# RcMPPT-Power_Module.net
KiCad netlist of a schematic drawn in Altium Designer
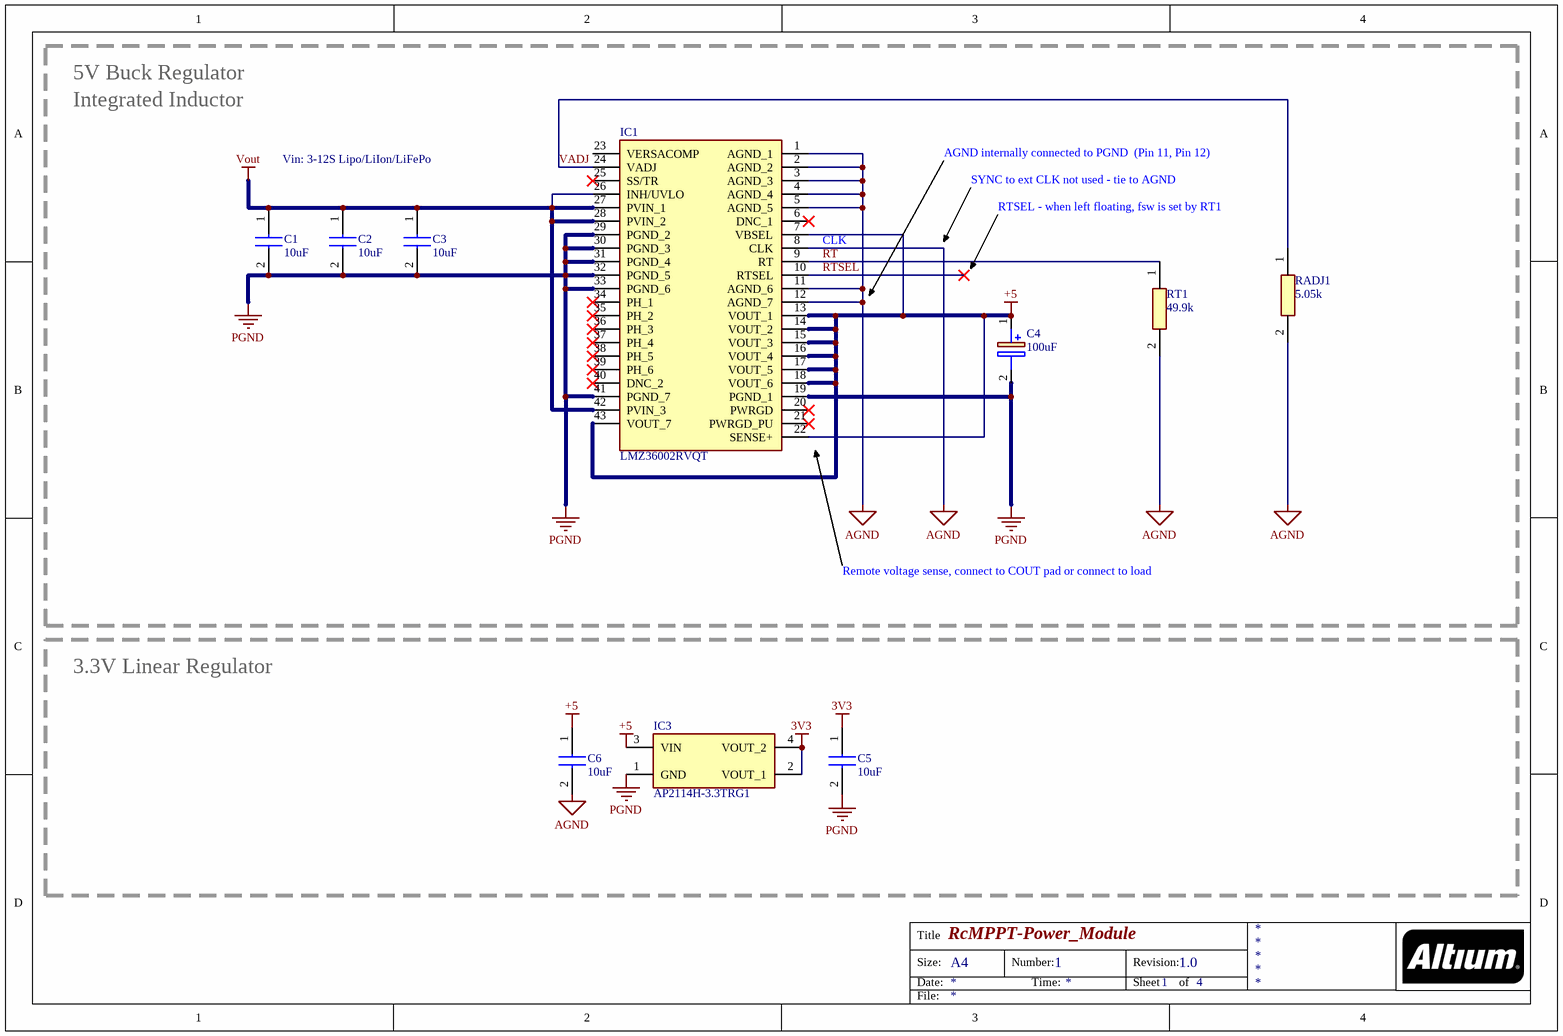
[diagram p0: RcMPPT-Power_Module.SchDoc]

(export (version "E")
  (design (tool "Eeschema 10.0.6"))
  (components
    (comp (ref "C1")
      (value "10uF")
      (footprint "RcMPPTLib:CAPC3225X280N")
      (description "Capacitor")
      (fields (field (name "MANUFACTURER_PART_NUMBER") "CL32B106KMVNNWE"))
      (libsource (lib "RcMPPTLib") (part "CL32B106KMVNNWE"))
    )
    (comp (ref "C2")
      (value "10uF")
      (footprint "RcMPPTLib:CAPC3225X280N")
      (description "Capacitor")
      (fields (field (name "MANUFACTURER_PART_NUMBER") "CL32B106KMVNNWE"))
      (libsource (lib "RcMPPTLib") (part "CL32B106KMVNNWE"))
    )
    (comp (ref "C3")
      (value "10uF")
      (footprint "RcMPPTLib:CAPC3225X280N")
      (description "Capacitor")
      (fields (field (name "MANUFACTURER_PART_NUMBER") "CL32B106KMVNNWE"))
      (libsource (lib "RcMPPTLib") (part "CL32B106KMVNNWE"))
    )
    (comp (ref "C4")
      (value "100uF")
      (footprint "CAPPM3528X200N")
      (description "Capacitor Polarised")
      (fields
        (field (name "MANUFACTURER_PART_NUMBER") "8TPE100MAZB")
        (field (name "MOUSER PART NUMBER") "667-8TPE100MAZB")
      )
      (libsource (lib "RcMPPTLib") (part "8TPE100MAZB"))
    )
    (comp (ref "C5")
      (value "10uF")
      (footprint "RcMPPTLib:CAPC3225X280N")
      (description "Capacitor")
      (fields (field (name "MANUFACTURER_PART_NUMBER") "CL32B106KMVNNWE"))
      (libsource (lib "RcMPPTLib") (part "CL32B106KMVNNWE"))
    )
    (comp (ref "C6")
      (value "10uF")
      (footprint "RcMPPTLib:CAPC3225X280N")
      (description "Capacitor")
      (fields (field (name "MANUFACTURER_PART_NUMBER") "CL32B106KMVNNWE"))
      (libsource (lib "RcMPPTLib") (part "CL32B106KMVNNWE"))
    )
    (comp (ref "IC1")
      (value "LMZ36002RVQT")
      (footprint "LMZ36002RVQR")
      (description "Integrated Circuit")
      (fields (field (name "MOUSER PART NUMBER") "595-LMZ36002RVQT"))
      (libsource (lib "RcMPPTLib") (part "LMZ36002RVQT"))
    )
    (comp (ref "IC3")
      (value "AP2114H-3.3TRG1")
      (footprint "SOT230P700X180-4N")
      (description "Integrated Circuit")
      (fields (field (name "MOUSER PART NUMBER") "621-AP2114H-3.3TRG1"))
      (libsource (lib "RcMPPTLib") (part "AP2114H-3.3TRG1"))
    )
    (comp (ref "RADJ1")
      (value "5.05k")
      (footprint "R0805")
      (description "Resistor")
      (fields
        (field (name "MANUFACTURER_PART_NUMBER") "RT0805BRD075K05L")
        (field (name "MOUSER PART NUMBER") "603-RT0805BRD075K05L")
      )
      (libsource (lib "RcMPPTLib") (part "RT0805BRD075K05L"))
    )
    (comp (ref "RT1")
      (value "49.9k")
      (footprint "RcMPPTLib:R0805")
      (description "Resistor")
      (fields
        (field (name "MANUFACTURER_PART_NUMBER") "ERJ-6ENF4992V")
        (field (name "MOUSER PART NUMBER") "667-ERJ-6ENF4992V")
      )
      (libsource (lib "RcMPPTLib") (part "ERJ-6ENF4992V"))
    )
  )
  (nets
    (net (code "1") (name "+5") (class "Default")
      (node (ref "C4") (pin "1") (pinfunction "+_1") (pintype "passive"))
      (node (ref "C6") (pin "1") (pinfunction "1_1") (pintype "passive"))
      (node (ref "IC1") (pin "13") (pinfunction "VOUT_1_13") (pintype "passive"))
      (node (ref "IC1") (pin "14") (pinfunction "VOUT_2_14") (pintype "passive"))
      (node (ref "IC1") (pin "15") (pinfunction "VOUT_3_15") (pintype "passive"))
      (node (ref "IC1") (pin "16") (pinfunction "VOUT_4_16") (pintype "passive"))
      (node (ref "IC1") (pin "17") (pinfunction "VOUT_5_17") (pintype "passive"))
      (node (ref "IC1") (pin "18") (pinfunction "VOUT_6_18") (pintype "passive"))
      (node (ref "IC1") (pin "22") (pinfunction "SENSE+_22") (pintype "passive"))
      (node (ref "IC1") (pin "43") (pinfunction "VOUT_7_43") (pintype "passive"))
      (node (ref "IC1") (pin "7") (pinfunction "VBSEL_7") (pintype "passive"))
      (node (ref "IC3") (pin "3") (pinfunction "VIN_3") (pintype "passive"))
    )
    (net (code "2") (name "/RT") (class "Default")
      (node (ref "IC1") (pin "9") (pinfunction "RT_9") (pintype "passive"))
      (node (ref "RT1") (pin "1") (pinfunction "1_1") (pintype "passive"))
    )
    (net (code "3") (name "/RTSEL") (class "Default")
      (node (ref "IC1") (pin "10") (pinfunction "RTSEL_10") (pintype "passive+no_connect"))
    )
    (net (code "4") (name "/VADJ") (class "Default")
      (node (ref "IC1") (pin "24") (pinfunction "VADJ_24") (pintype "passive"))
      (node (ref "RADJ1") (pin "1") (pinfunction "1_1") (pintype "passive"))
    )
    (net (code "5") (name "3V3") (class "Default")
      (node (ref "C5") (pin "1") (pinfunction "1_1") (pintype "passive"))
      (node (ref "IC3") (pin "2") (pinfunction "VOUT_1_2") (pintype "passive"))
      (node (ref "IC3") (pin "4") (pinfunction "VOUT_2_4") (pintype "passive"))
    )
    (net (code "6") (name "AGND") (class "Default")
      (node (ref "C6") (pin "2") (pinfunction "2_2") (pintype "passive"))
      (node (ref "IC1") (pin "1") (pinfunction "AGND_1_1") (pintype "passive"))
      (node (ref "IC1") (pin "11") (pinfunction "AGND_6_11") (pintype "passive"))
      (node (ref "IC1") (pin "12") (pinfunction "AGND_7_12") (pintype "passive"))
      (node (ref "IC1") (pin "2") (pinfunction "AGND_2_2") (pintype "passive"))
      (node (ref "IC1") (pin "3") (pinfunction "AGND_3_3") (pintype "passive"))
      (node (ref "IC1") (pin "4") (pinfunction "AGND_4_4") (pintype "passive"))
      (node (ref "IC1") (pin "5") (pinfunction "AGND_5_5") (pintype "passive"))
      (node (ref "IC1") (pin "8") (pinfunction "CLK_8") (pintype "passive"))
      (node (ref "RADJ1") (pin "2") (pinfunction "2_2") (pintype "passive"))
      (node (ref "RT1") (pin "2") (pinfunction "2_2") (pintype "passive"))
    )
    (net (code "7") (name "PGND") (class "Default")
      (node (ref "C1") (pin "2") (pinfunction "2_2") (pintype "passive"))
      (node (ref "C2") (pin "2") (pinfunction "2_2") (pintype "passive"))
      (node (ref "C3") (pin "2") (pinfunction "2_2") (pintype "passive"))
      (node (ref "C4") (pin "2") (pinfunction "-_2") (pintype "passive"))
      (node (ref "C5") (pin "2") (pinfunction "2_2") (pintype "passive"))
      (node (ref "IC1") (pin "19") (pinfunction "PGND_1_19") (pintype "passive"))
      (node (ref "IC1") (pin "29") (pinfunction "PGND_2_29") (pintype "passive"))
      (node (ref "IC1") (pin "30") (pinfunction "PGND_3_30") (pintype "passive"))
      (node (ref "IC1") (pin "31") (pinfunction "PGND_4_31") (pintype "passive"))
      (node (ref "IC1") (pin "32") (pinfunction "PGND_5_32") (pintype "passive"))
      (node (ref "IC1") (pin "33") (pinfunction "PGND_6_33") (pintype "passive"))
      (node (ref "IC1") (pin "41") (pinfunction "PGND_7_41") (pintype "passive"))
      (node (ref "IC3") (pin "1") (pinfunction "GND_1") (pintype "passive"))
    )
    (net (code "8") (name "Vout") (class "Default")
      (node (ref "C1") (pin "1") (pinfunction "1_1") (pintype "passive"))
      (node (ref "C2") (pin "1") (pinfunction "1_1") (pintype "passive"))
      (node (ref "C3") (pin "1") (pinfunction "1_1") (pintype "passive"))
      (node (ref "IC1") (pin "26") (pinfunction "INH/UVLO_26") (pintype "passive"))
      (node (ref "IC1") (pin "27") (pinfunction "PVIN_1_27") (pintype "passive"))
      (node (ref "IC1") (pin "28") (pinfunction "PVIN_2_28") (pintype "passive"))
      (node (ref "IC1") (pin "42") (pinfunction "PVIN_3_42") (pintype "passive"))
    )
    (net (code "9") (name "unconnected-(IC1-DNC_1-Pad6)") (class "Default")
      (node (ref "IC1") (pin "6") (pinfunction "DNC_1_6") (pintype "passive+no_connect"))
    )
    (net (code "10") (name "unconnected-(IC1-DNC_2-Pad40)") (class "Default")
      (node (ref "IC1") (pin "40") (pinfunction "DNC_2_40") (pintype "passive+no_connect"))
    )
    (net (code "11") (name "unconnected-(IC1-PH_1-Pad34)") (class "Default")
      (node (ref "IC1") (pin "34") (pinfunction "PH_1_34") (pintype "passive+no_connect"))
    )
    (net (code "12") (name "unconnected-(IC1-PH_2-Pad35)") (class "Default")
      (node (ref "IC1") (pin "35") (pinfunction "PH_2_35") (pintype "passive+no_connect"))
    )
    (net (code "13") (name "unconnected-(IC1-PH_3-Pad36)") (class "Default")
      (node (ref "IC1") (pin "36") (pinfunction "PH_3_36") (pintype "passive+no_connect"))
    )
    (net (code "14") (name "unconnected-(IC1-PH_4-Pad37)") (class "Default")
      (node (ref "IC1") (pin "37") (pinfunction "PH_4_37") (pintype "passive+no_connect"))
    )
    (net (code "15") (name "unconnected-(IC1-PH_5-Pad38)") (class "Default")
      (node (ref "IC1") (pin "38") (pinfunction "PH_5_38") (pintype "passive+no_connect"))
    )
    (net (code "16") (name "unconnected-(IC1-PH_6-Pad39)") (class "Default")
      (node (ref "IC1") (pin "39") (pinfunction "PH_6_39") (pintype "passive+no_connect"))
    )
    (net (code "17") (name "unconnected-(IC1-PWRGD-Pad20)") (class "Default")
      (node (ref "IC1") (pin "20") (pinfunction "PWRGD_20") (pintype "passive+no_connect"))
    )
    (net (code "18") (name "unconnected-(IC1-PWRGD_PU-Pad21)") (class "Default")
      (node (ref "IC1") (pin "21") (pinfunction "PWRGD_PU_21") (pintype "passive+no_connect"))
    )
    (net (code "19") (name "unconnected-(IC1-SS{slash}TR-Pad25)") (class "Default")
      (node (ref "IC1") (pin "25") (pinfunction "SS/TR_25") (pintype "passive+no_connect"))
    )
    (net (code "20") (name "unconnected-(IC1-VERSACOMP-Pad23)") (class "Default")
      (node (ref "IC1") (pin "23") (pinfunction "VERSACOMP_23") (pintype "passive"))
    )
  )
)
